# ArbPwrBoost_P5.net
KiCad netlist of a schematic drawn in Altium Designer
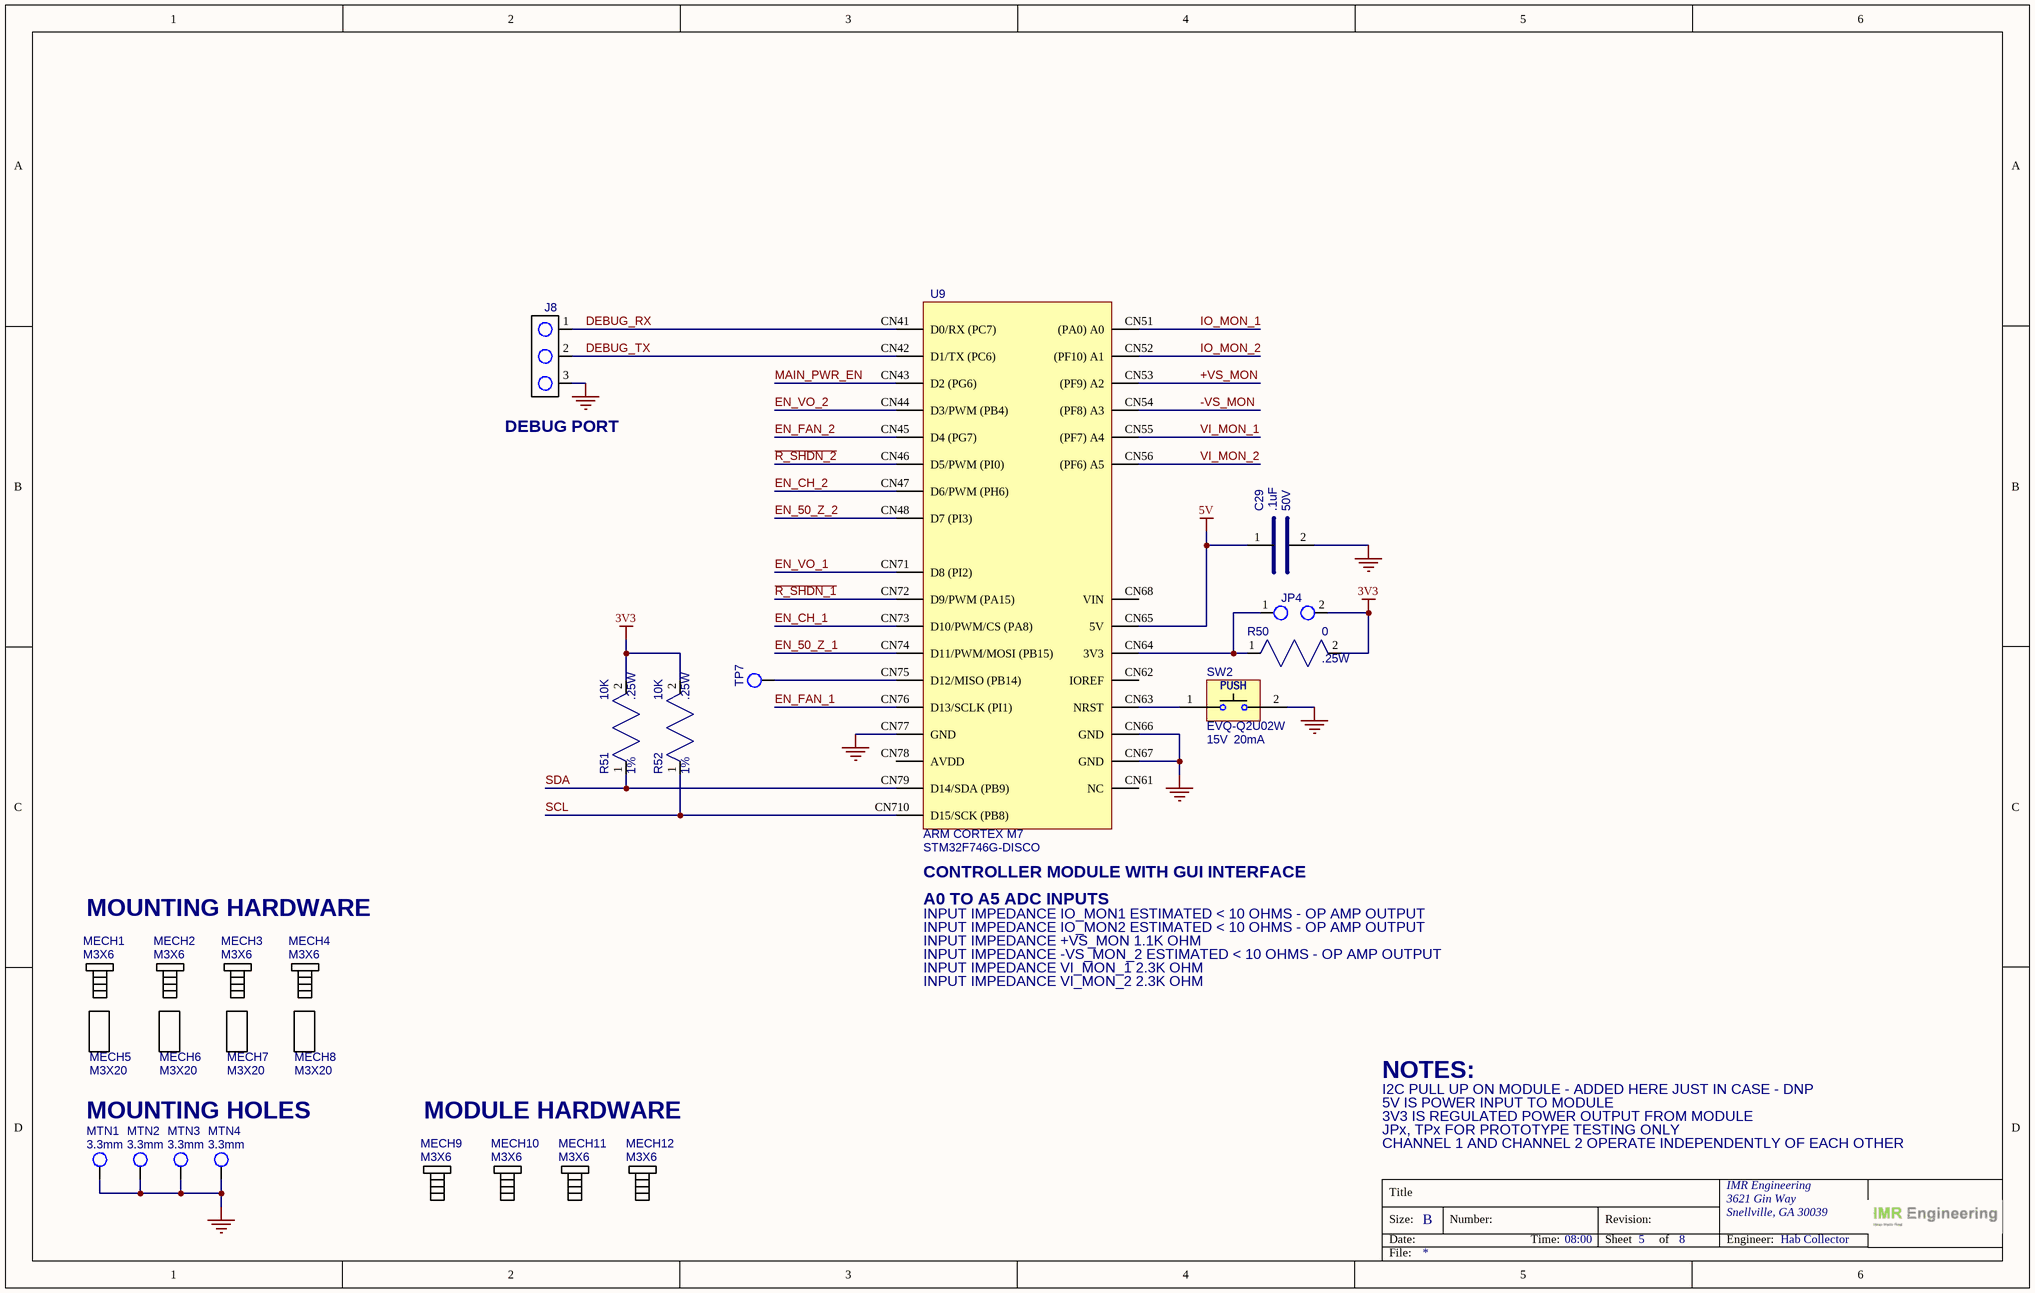
[diagram p0: ArbPwrBoost_P5.SchDoc]

(export (version "E")
  (design (tool "Eeschema 10.0.6"))
  (components
    (comp (ref "C29")
      (value ".1uF")
      (footprint "CAP_0805")
      (description "CAP CER 0.1UF 50V X7R 0805")
      (fields
        (field (name "MFG") "KYOCERA AVX")
        (field (name "VOLTAGE") "50V")
        (field (name "Comment") "KGM21NR71H104KT")
      )
      (libsource (lib "IMR_LIB_SCH_R2") (part "CAP_SMD_0.1UF_50V_0805"))
    )
    (comp (ref "J8")
      (value "PREC003SFAN-RC")
      (footprint "HDR_1X3_100MILL")
      (description "CONN HEADER VERT 3POS 2.54MM")
      (fields (field (name "MFG") "Sullins Connector Solutions"))
      (libsource (lib "IMR_LIB_SCH_R2") (part "CONN_HEADER_3P_100MIL_VERT"))
    )
    (comp (ref "JP4")
      (value "PREC002SFAN-RC")
      (footprint "HDR_1X2_100MILL")
      (description "CONN HEADER VERT 2POS 2.54MM")
      (fields (field (name "MFG") "Sullins Connector Solutions"))
      (libsource (lib "IMR_LIB_SCH_R2") (part "CONN_JUMPER_2P_100MIL_VERT"))
    )
    (comp (ref "MECH1")
      (value "RM3X6MM 2701")
      (footprint "MECHANICAL_SCREW_M3X6")
      (description "SCREW M3X6 PAN HEAD SS")
      (fields (field (name "MFG") "APM Hexseal") (field (name "SIZE") "M3X6"))
      (libsource (lib "IMR_LIB_SCH_R2") (part "MECHANICAL_SCREW_M3X6_PAN_HEAD"))
    )
    (comp (ref "MECH2")
      (value "RM3X6MM 2701")
      (footprint "MECHANICAL_SCREW_M3X6")
      (description "SCREW M3X6 PAN HEAD SS")
      (fields (field (name "MFG") "APM Hexseal") (field (name "SIZE") "M3X6"))
      (libsource (lib "IMR_LIB_SCH_R2") (part "MECHANICAL_SCREW_M3X6_PAN_HEAD"))
    )
    (comp (ref "MECH3")
      (value "RM3X6MM 2701")
      (footprint "MECHANICAL_SCREW_M3X6")
      (description "SCREW M3X6 PAN HEAD SS")
      (fields (field (name "MFG") "APM Hexseal") (field (name "SIZE") "M3X6"))
      (libsource (lib "IMR_LIB_SCH_R2") (part "MECHANICAL_SCREW_M3X6_PAN_HEAD"))
    )
    (comp (ref "MECH4")
      (value "RM3X6MM 2701")
      (footprint "MECHANICAL_SCREW_M3X6")
      (description "SCREW M3X6 PAN HEAD SS")
      (fields (field (name "MFG") "APM Hexseal") (field (name "SIZE") "M3X6"))
      (libsource (lib "IMR_LIB_SCH_R2") (part "MECHANICAL_SCREW_M3X6_PAN_HEAD"))
    )
    (comp (ref "MECH5")
      (value "24407")
      (footprint "MECHANICAL_SPACER_F_F_M3X20")
      (description "HEX STANDOFF M3 BRASS 20MM")
      (fields (field (name "MFG") "Keystone Electronics") (field (name "SIZE") "M3X20"))
      (libsource (lib "IMR_LIB_SCH_R2") (part "MECHANICAL_STANDOFF_M3X20"))
    )
    (comp (ref "MECH6")
      (value "24407")
      (footprint "MECHANICAL_SPACER_F_F_M3X20")
      (description "HEX STANDOFF M3 BRASS 20MM")
      (fields (field (name "MFG") "Keystone Electronics") (field (name "SIZE") "M3X20"))
      (libsource (lib "IMR_LIB_SCH_R2") (part "MECHANICAL_STANDOFF_M3X20"))
    )
    (comp (ref "MECH7")
      (value "24407")
      (footprint "MECHANICAL_SPACER_F_F_M3X20")
      (description "HEX STANDOFF M3 BRASS 20MM")
      (fields (field (name "MFG") "Keystone Electronics") (field (name "SIZE") "M3X20"))
      (libsource (lib "IMR_LIB_SCH_R2") (part "MECHANICAL_STANDOFF_M3X20"))
    )
    (comp (ref "MECH8")
      (value "24407")
      (footprint "MECHANICAL_SPACER_F_F_M3X20")
      (description "HEX STANDOFF M3 BRASS 20MM")
      (fields (field (name "MFG") "Keystone Electronics") (field (name "SIZE") "M3X20"))
      (libsource (lib "IMR_LIB_SCH_R2") (part "MECHANICAL_STANDOFF_M3X20"))
    )
    (comp (ref "MECH9")
      (value "RM3X6MM 2701")
      (footprint "MECHANICAL_SCREW_M3X6")
      (description "SCREW M3X6 PAN HEAD SS")
      (fields (field (name "MFG") "APM Hexseal") (field (name "SIZE") "M3X6"))
      (libsource (lib "IMR_LIB_SCH_R2") (part "MECHANICAL_SCREW_M3X6_PAN_HEAD"))
    )
    (comp (ref "MECH10")
      (value "RM3X6MM 2701")
      (footprint "MECHANICAL_SCREW_M3X6")
      (description "SCREW M3X6 PAN HEAD SS")
      (fields (field (name "MFG") "APM Hexseal") (field (name "SIZE") "M3X6"))
      (libsource (lib "IMR_LIB_SCH_R2") (part "MECHANICAL_SCREW_M3X6_PAN_HEAD"))
    )
    (comp (ref "MECH11")
      (value "RM3X6MM 2701")
      (footprint "MECHANICAL_SCREW_M3X6")
      (description "SCREW M3X6 PAN HEAD SS")
      (fields (field (name "MFG") "APM Hexseal") (field (name "SIZE") "M3X6"))
      (libsource (lib "IMR_LIB_SCH_R2") (part "MECHANICAL_SCREW_M3X6_PAN_HEAD"))
    )
    (comp (ref "MECH12")
      (value "RM3X6MM 2701")
      (footprint "MECHANICAL_SCREW_M3X6")
      (description "SCREW M3X6 PAN HEAD SS")
      (fields (field (name "MFG") "APM Hexseal") (field (name "SIZE") "M3X6"))
      (libsource (lib "IMR_LIB_SCH_R2") (part "MECHANICAL_SCREW_M3X6_PAN_HEAD"))
    )
    (comp (ref "MTN1")
      (value "~")
      (footprint "PMG_MT_HOLE_3.3MM")
      (description "MOUNTING HOLE 3.3MM")
      (fields (field (name "HOLE SIZE") "3.3mm"))
      (libsource (lib "IMR_LIB_SCH_R2") (part "MTN_HOLE_3.3MM"))
    )
    (comp (ref "MTN2")
      (value "~")
      (footprint "PMG_MT_HOLE_3.3MM")
      (description "MOUNTING HOLE 3.3MM")
      (fields (field (name "HOLE SIZE") "3.3mm"))
      (libsource (lib "IMR_LIB_SCH_R2") (part "MTN_HOLE_3.3MM"))
    )
    (comp (ref "MTN3")
      (value "~")
      (footprint "PMG_MT_HOLE_3.3MM")
      (description "MOUNTING HOLE 3.3MM")
      (fields (field (name "HOLE SIZE") "3.3mm"))
      (libsource (lib "IMR_LIB_SCH_R2") (part "MTN_HOLE_3.3MM"))
    )
    (comp (ref "MTN4")
      (value "~")
      (footprint "PMG_MT_HOLE_3.3MM")
      (description "MOUNTING HOLE 3.3MM")
      (fields (field (name "HOLE SIZE") "3.3mm"))
      (libsource (lib "IMR_LIB_SCH_R2") (part "MTN_HOLE_3.3MM"))
    )
    (comp (ref "R50")
      (value "0")
      (footprint "RES_0805")
      (description "RES SMD 0 OHM 1% 1/8W 0805")
      (fields (field (name "MFG") "Yageo") (field (name "TOLERANCE") "1%") (field (name "POWER") ".25W"))
      (libsource (lib "IMR_LIB_SCH_R2") (part "RES_SMD_0_0805_1/8W_1%"))
    )
    (comp (ref "R51")
      (value "10K")
      (footprint "RES_0805")
      (description "RES SMD 10K OHM 1% 1/4W 0805")
      (fields
        (field (name "MFG") "Yageo")
        (field (name "POWER") ".25W")
        (field (name "TOLERANCE") "1%")
        (field (name "Comment") "RC0805FR-7W10KL")
      )
      (libsource (lib "IMR_LIB_SCH_R2") (part "RES_SMD_10K_0805_1/4W_1%"))
    )
    (comp (ref "R52")
      (value "10K")
      (footprint "RES_0805")
      (description "RES SMD 10K OHM 1% 1/4W 0805")
      (fields
        (field (name "MFG") "Yageo")
        (field (name "POWER") ".25W")
        (field (name "TOLERANCE") "1%")
        (field (name "Comment") "RC0805FR-7W10KL")
      )
      (libsource (lib "IMR_LIB_SCH_R2") (part "RES_SMD_10K_0805_1/4W_1%"))
    )
    (comp (ref "SW2")
      (value "15V")
      (footprint "PANASONIC_EVQ-Q2U02W")
      (description "SWITCH TACTILE SPST-NO 0.02A 15V")
      (fields
        (field (name "MFG") "American Zettler")
        (field (name "MFG_PN") "EVQ-Q2U02W")
        (field (name "CURRENT") "20mA")
        (field (name "Comment") "EVQ-Q2U02W")
      )
      (libsource (lib "IMR_LIB_SCH_R2") (part "SWITCH_EVQ-Q2U02W"))
    )
    (comp (ref "TP7")
      (value "~")
      (footprint "TEST_POINT_20MIL_TH")
      (description "TEST POINT TH 20MIL HOLE")
      (libsource (lib "IMR_LIB_SCH_R2") (part "CONN_TEST_POINT_TH_PAD_20MIL"))
    )
    (comp (ref "U9")
      (value "ARM CORTEX M7")
      (footprint "STM32F746G-DISCO")
      (description "DISCOVERY STM32 F7 EVAL BRD")
      (fields
        (field (name "MFG") "ST Microlectronics")
        (field (name "MFG_PN") "STM32F746G-DISCO")
        (field (name "Comment") "STM32F746G-DISCO")
      )
      (libsource (lib "IMR_LIB_SCH_R2") (part "MODULE_STM32F746G-DISCO"))
    )
  )
  (nets
    (net (code "1") (name "/+VS_MON") (class "Default")
      (node (ref "U9") (pin "CN53") (pinfunction "(PF9)_A2_CN53") (pintype "passive"))
    )
    (net (code "2") (name "/-VS_MON") (class "Default")
      (node (ref "U9") (pin "CN54") (pinfunction "(PF8)_A3_CN54") (pintype "passive"))
    )
    (net (code "3") (name "/DEBUG_RX") (class "Default")
      (node (ref "J8") (pin "1") (pintype "passive"))
      (node (ref "U9") (pin "CN41") (pinfunction "D0/RX_(PC7)_CN41") (pintype "passive"))
    )
    (net (code "4") (name "/DEBUG_TX") (class "Default")
      (node (ref "J8") (pin "2") (pintype "passive"))
      (node (ref "U9") (pin "CN42") (pinfunction "D1/TX_(PC6)_CN42") (pintype "passive"))
    )
    (net (code "5") (name "/EN_50_Z_1") (class "Default")
      (node (ref "U9") (pin "CN74") (pinfunction "D11/PWM/MOSI_(PB15)_CN74") (pintype "passive"))
    )
    (net (code "6") (name "/EN_50_Z_2") (class "Default")
      (node (ref "U9") (pin "CN48") (pinfunction "D7_(PI3)_CN48") (pintype "passive"))
    )
    (net (code "7") (name "/EN_CH_1") (class "Default")
      (node (ref "U9") (pin "CN73") (pinfunction "D10/PWM/CS_(PA8)_CN73") (pintype "passive"))
    )
    (net (code "8") (name "/EN_CH_2") (class "Default")
      (node (ref "U9") (pin "CN47") (pinfunction "D6/PWM_(PH6)_CN47") (pintype "passive"))
    )
    (net (code "9") (name "/EN_FAN_1") (class "Default")
      (node (ref "U9") (pin "CN76") (pinfunction "D13/SCLK_(PI1)_CN76") (pintype "passive"))
    )
    (net (code "10") (name "/EN_FAN_2") (class "Default")
      (node (ref "U9") (pin "CN45") (pinfunction "D4_(PG7)_CN45") (pintype "passive"))
    )
    (net (code "11") (name "/EN_VO_1") (class "Default")
      (node (ref "U9") (pin "CN71") (pinfunction "D8_(PI2)_CN71") (pintype "passive"))
    )
    (net (code "12") (name "/EN_VO_2") (class "Default")
      (node (ref "U9") (pin "CN44") (pinfunction "D3/PWM_(PB4)_CN44") (pintype "passive"))
    )
    (net (code "13") (name "/IO_MON_1") (class "Default")
      (node (ref "U9") (pin "CN51") (pinfunction "(PA0)_A0_CN51") (pintype "passive"))
    )
    (net (code "14") (name "/IO_MON_2") (class "Default")
      (node (ref "U9") (pin "CN52") (pinfunction "(PF10)_A1_CN52") (pintype "passive"))
    )
    (net (code "15") (name "/MAIN_PWR_EN") (class "Default")
      (node (ref "U9") (pin "CN43") (pinfunction "D2_(PG6)_CN43") (pintype "passive"))
    )
    (net (code "16") (name "/SCL") (class "Default")
      (node (ref "R52") (pin "1") (pinfunction "1_1") (pintype "passive"))
      (node (ref "U9") (pin "CN710") (pinfunction "D15/SCK_(PB8)_CN710") (pintype "passive"))
    )
    (net (code "17") (name "/SDA") (class "Default")
      (node (ref "R51") (pin "1") (pinfunction "1_1") (pintype "passive"))
      (node (ref "U9") (pin "CN79") (pinfunction "D14/SDA_(PB9)_CN79") (pintype "passive"))
    )
    (net (code "18") (name "/VI_MON_1") (class "Default")
      (node (ref "U9") (pin "CN55") (pinfunction "(PF7)_A4_CN55") (pintype "passive"))
    )
    (net (code "19") (name "/VI_MON_2") (class "Default")
      (node (ref "U9") (pin "CN56") (pinfunction "(PF6)_A5_CN56") (pintype "passive"))
    )
    (net (code "20") (name "/~{R_SHDN_1}") (class "Default")
      (node (ref "U9") (pin "CN72") (pinfunction "D9/PWM_(PA15)_CN72") (pintype "passive"))
    )
    (net (code "21") (name "/~{R_SHDN_2}") (class "Default")
      (node (ref "U9") (pin "CN46") (pinfunction "D5/PWM_(PI0)_CN46") (pintype "passive"))
    )
    (net (code "22") (name "3V3") (class "Default")
      (node (ref "JP4") (pin "2") (pintype "passive"))
      (node (ref "R50") (pin "2") (pinfunction "2_2") (pintype "passive"))
      (node (ref "R51") (pin "2") (pinfunction "2_2") (pintype "passive"))
      (node (ref "R52") (pin "2") (pinfunction "2_2") (pintype "passive"))
    )
    (net (code "23") (name "5V") (class "Default")
      (node (ref "C29") (pin "1") (pinfunction "1_1") (pintype "passive"))
      (node (ref "U9") (pin "CN65") (pinfunction "5V_CN65") (pintype "passive"))
    )
    (net (code "24") (name "GND") (class "Default")
      (node (ref "C29") (pin "2") (pinfunction "2_2") (pintype "passive"))
      (node (ref "J8") (pin "3") (pintype "passive"))
      (node (ref "MTN1") (pin "1") (pintype "passive"))
      (node (ref "MTN2") (pin "1") (pintype "passive"))
      (node (ref "MTN3") (pin "1") (pintype "passive"))
      (node (ref "MTN4") (pin "1") (pintype "passive"))
      (node (ref "SW2") (pin "2") (pinfunction "B'_2") (pintype "passive"))
      (node (ref "U9") (pin "CN66") (pinfunction "GND_CN66") (pintype "passive"))
      (node (ref "U9") (pin "CN67") (pinfunction "GND_CN67") (pintype "passive"))
      (node (ref "U9") (pin "CN77") (pinfunction "GND_CN77") (pintype "passive"))
    )
    (net (code "25") (name "Net-(SW2-B)") (class "Default")
      (node (ref "SW2") (pin "1") (pinfunction "B_1") (pintype "passive"))
      (node (ref "U9") (pin "CN63") (pinfunction "NRST_CN63") (pintype "passive"))
    )
    (net (code "26") (name "Net-(U9-3V3)") (class "Default")
      (node (ref "JP4") (pin "1") (pintype "passive"))
      (node (ref "R50") (pin "1") (pinfunction "1_1") (pintype "passive"))
      (node (ref "U9") (pin "CN64") (pinfunction "3V3_CN64") (pintype "passive"))
    )
    (net (code "27") (name "Net-(U9-D12{slash}MISO_(PB14))") (class "Default")
      (node (ref "TP7") (pin "1") (pintype "passive"))
      (node (ref "U9") (pin "CN75") (pinfunction "D12/MISO_(PB14)_CN75") (pintype "passive"))
    )
    (net (code "28") (name "unconnected-(U9-AVDD-PadCN78)") (class "Default")
      (node (ref "U9") (pin "CN78") (pinfunction "AVDD_CN78") (pintype "passive"))
    )
    (net (code "29") (name "unconnected-(U9-IOREF-PadCN62)") (class "Default")
      (node (ref "U9") (pin "CN62") (pinfunction "IOREF_CN62") (pintype "passive"))
    )
    (net (code "30") (name "unconnected-(U9-NC-PadCN61)") (class "Default")
      (node (ref "U9") (pin "CN61") (pinfunction "NC_CN61") (pintype "passive"))
    )
    (net (code "31") (name "unconnected-(U9-VIN-PadCN68)") (class "Default")
      (node (ref "U9") (pin "CN68") (pinfunction "VIN_CN68") (pintype "passive"))
    )
  )
)
